# Audio_Moduloop.net
KiCad netlist of a schematic drawn in Altium Designer
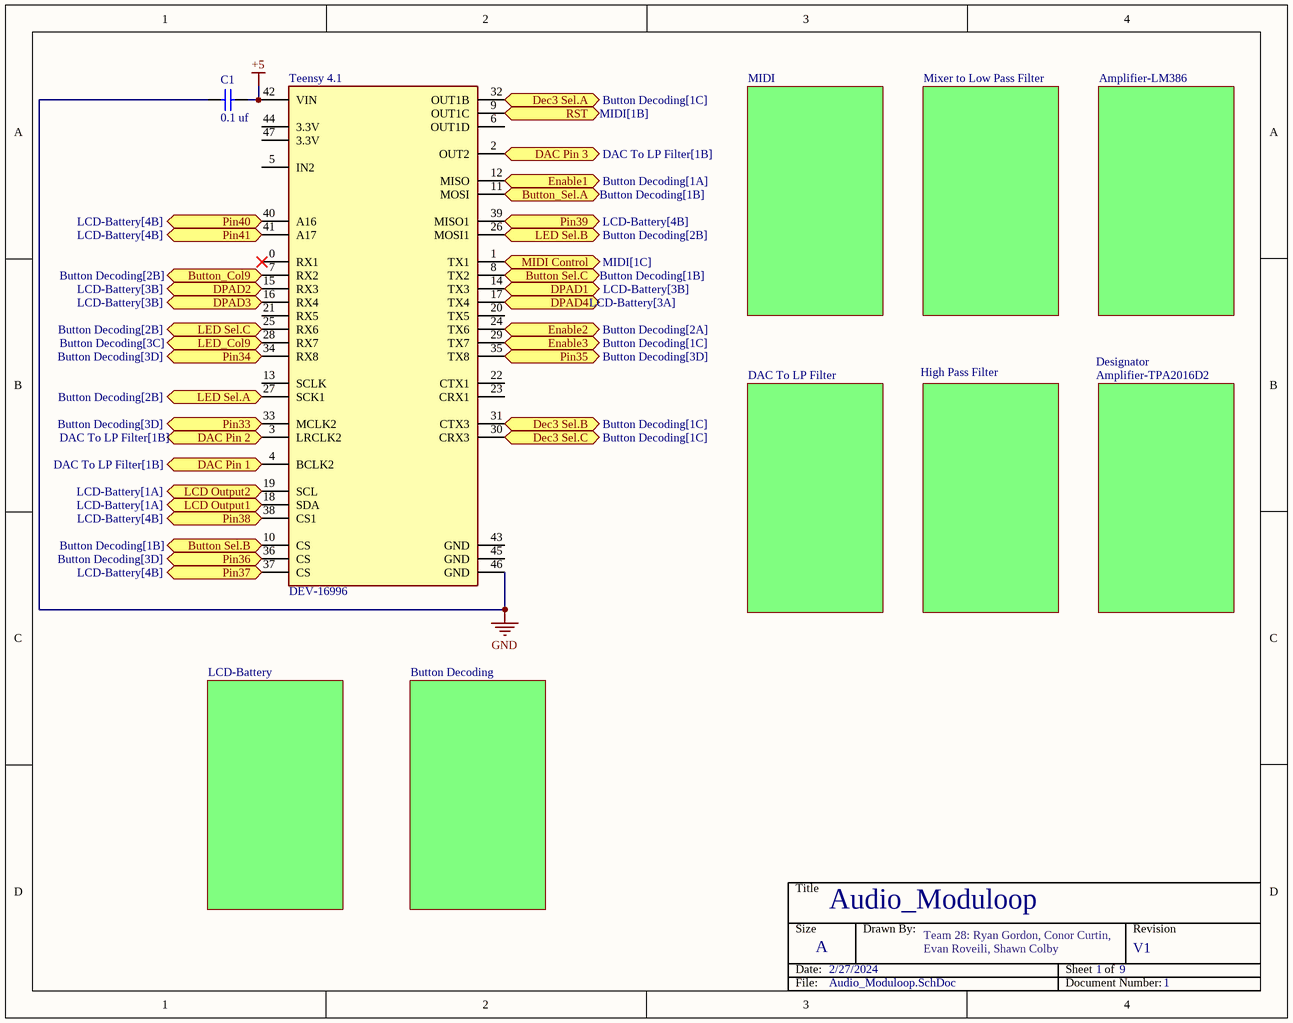
[diagram p0: Audio_Moduloop.SchDoc]

(export (version "E")
  (design (tool "Eeschema 10.0.6"))
  (components
    (comp (ref "C1")
      (value "0.1 uf")
      (footprint "CAPC2013X135X45ML10T25")
      (description "Chip Capacitor, 0.1 uF, +/- 10%, 50 V, -55 to 125 degC, 0805 (2012 Metric), RoHS, Tape and Reel")
      (fields (field (name "VOLTAGE") "50V") (field (name "TOLERANCE") "10%"))
      (libsource (lib "Altium Content Vault") (part "CAP-NP-2"))
    )
    (comp (ref "Teensy 4.1")
      (value "DEV-16996")
      (footprint "FP-DEV-16996-MFG")
      (description "TEENSY 4.1 (HEADERS)")
      (libsource (lib "Altium Content Vault") (part "080115a1ce54750370cf87ec145ee29"))
    )
  )
  (nets
    (net (code "1") (name "+5") (class "Default")
      (node (ref "C1") (pin "1") (pinfunction "1_1") (pintype "passive"))
      (node (ref "Teensy 4.1") (pin "42") (pinfunction "VIN_42") (pintype "passive"))
    )
    (net (code "2") (name "/Button Sel.B") (class "Default")
      (node (ref "Teensy 4.1") (pin "10") (pinfunction "CS_10") (pintype "passive"))
    )
    (net (code "4") (name "/Button Sel.C") (class "Default")
      (node (ref "Teensy 4.1") (pin "8") (pinfunction "TX2_8") (pintype "passive"))
    )
    (net (code "6") (name "/Button_Col9") (class "Default")
      (node (ref "Teensy 4.1") (pin "7") (pinfunction "RX2_7") (pintype "passive"))
    )
    (net (code "7") (name "/Button_Sel.A") (class "Default")
      (node (ref "Teensy 4.1") (pin "11") (pinfunction "MOSI_11") (pintype "passive"))
    )
    (net (code "10") (name "/DAC Pin 1") (class "Default")
      (node (ref "Teensy 4.1") (pin "4") (pinfunction "BCLK2_4") (pintype "passive"))
    )
    (net (code "11") (name "/DAC Pin 2") (class "Default")
      (node (ref "Teensy 4.1") (pin "3") (pinfunction "LRCLK2_3") (pintype "passive"))
    )
    (net (code "19") (name "/DAC Pin 3") (class "Default")
      (node (ref "Teensy 4.1") (pin "2") (pinfunction "OUT2_2") (pintype "passive"))
    )
    (net (code "20") (name "/DPAD1") (class "Default")
      (node (ref "Teensy 4.1") (pin "14") (pinfunction "TX3_14") (pintype "passive"))
    )
    (net (code "21") (name "/DPAD2") (class "Default")
      (node (ref "Teensy 4.1") (pin "15") (pinfunction "RX3_15") (pintype "passive"))
    )
    (net (code "23") (name "/DPAD3") (class "Default")
      (node (ref "Teensy 4.1") (pin "16") (pinfunction "RX4_16") (pintype "passive"))
    )
    (net (code "24") (name "/DPAD4") (class "Default")
      (node (ref "Teensy 4.1") (pin "17") (pinfunction "TX4_17") (pintype "passive"))
    )
    (net (code "26") (name "/Dec3 Sel.A") (class "Default")
      (node (ref "Teensy 4.1") (pin "32") (pinfunction "OUT1B_32") (pintype "passive"))
    )
    (net (code "27") (name "/Dec3 Sel.B") (class "Default")
      (node (ref "Teensy 4.1") (pin "31") (pinfunction "CTX3_31") (pintype "passive"))
    )
    (net (code "29") (name "/Dec3 Sel.C") (class "Default")
      (node (ref "Teensy 4.1") (pin "30") (pinfunction "CRX3_30") (pintype "passive"))
    )
    (net (code "30") (name "/Enable1") (class "Default")
      (node (ref "Teensy 4.1") (pin "12") (pinfunction "MISO_12") (pintype "passive"))
    )
    (net (code "31") (name "/Enable2") (class "Default")
      (node (ref "Teensy 4.1") (pin "24") (pinfunction "TX6_24") (pintype "passive"))
    )
    (net (code "33") (name "/Enable3") (class "Default")
      (node (ref "Teensy 4.1") (pin "29") (pinfunction "TX7_29") (pintype "passive"))
    )
    (net (code "34") (name "/LCD Output1") (class "Default")
      (node (ref "Teensy 4.1") (pin "18") (pinfunction "SDA_18") (pintype "passive"))
    )
    (net (code "36") (name "/LCD Output2") (class "Default")
      (node (ref "Teensy 4.1") (pin "19") (pinfunction "SCL_19") (pintype "passive"))
    )
    (net (code "37") (name "/LED Sel.A") (class "Default")
      (node (ref "Teensy 4.1") (pin "27") (pinfunction "SCK1_27") (pintype "passive"))
    )
    (net (code "38") (name "/LED Sel.B") (class "Default")
      (node (ref "Teensy 4.1") (pin "26") (pinfunction "MOSI1_26") (pintype "passive"))
    )
    (net (code "39") (name "/LED Sel.C") (class "Default")
      (node (ref "Teensy 4.1") (pin "25") (pinfunction "RX6_25") (pintype "passive"))
    )
    (net (code "40") (name "/LED_Col9") (class "Default")
      (node (ref "Teensy 4.1") (pin "28") (pinfunction "RX7_28") (pintype "passive"))
    )
    (net (code "41") (name "/MIDI Control") (class "Default")
      (node (ref "Teensy 4.1") (pin "1") (pinfunction "TX1_1") (pintype "passive"))
    )
    (net (code "42") (name "/Pin33") (class "Default")
      (node (ref "Teensy 4.1") (pin "33") (pinfunction "MCLK2_33") (pintype "passive"))
    )
    (net (code "43") (name "/Pin34") (class "Default")
      (node (ref "Teensy 4.1") (pin "34") (pinfunction "RX8_34") (pintype "passive"))
    )
    (net (code "44") (name "/Pin35") (class "Default")
      (node (ref "Teensy 4.1") (pin "35") (pinfunction "TX8_35") (pintype "passive"))
    )
    (net (code "45") (name "/Pin36") (class "Default")
      (node (ref "Teensy 4.1") (pin "36") (pinfunction "CS_36") (pintype "passive"))
    )
    (net (code "46") (name "/Pin37") (class "Default")
      (node (ref "Teensy 4.1") (pin "37") (pinfunction "CS_37") (pintype "passive"))
    )
    (net (code "47") (name "/Pin38") (class "Default")
      (node (ref "Teensy 4.1") (pin "38") (pinfunction "CS1_38") (pintype "passive"))
    )
    (net (code "48") (name "/Pin39") (class "Default")
      (node (ref "Teensy 4.1") (pin "39") (pinfunction "MISO1_39") (pintype "passive"))
    )
    (net (code "49") (name "/Pin40") (class "Default")
      (node (ref "Teensy 4.1") (pin "40") (pinfunction "A16_40") (pintype "passive"))
    )
    (net (code "50") (name "/Pin41") (class "Default")
      (node (ref "Teensy 4.1") (pin "41") (pinfunction "A17_41") (pintype "passive"))
    )
    (net (code "51") (name "/RST") (class "Default")
      (node (ref "Teensy 4.1") (pin "9") (pinfunction "OUT1C_9") (pintype "passive"))
    )
    (net (code "52") (name "GND") (class "Default")
      (node (ref "C1") (pin "2") (pinfunction "2_2") (pintype "passive"))
      (node (ref "Teensy 4.1") (pin "46") (pinfunction "GND_46") (pintype "passive"))
    )
    (net (code "53") (name "unconnected-(Teensy 4.1-3.3V-Pad44)") (class "Default")
      (node (ref "Teensy 4.1") (pin "44") (pinfunction "3.3V_44") (pintype "passive"))
    )
    (net (code "54") (name "unconnected-(Teensy 4.1-3.3V-Pad47)") (class "Default")
      (node (ref "Teensy 4.1") (pin "47") (pinfunction "3.3V_47") (pintype "passive"))
    )
    (net (code "55") (name "unconnected-(Teensy 4.1-CRX1-Pad23)") (class "Default")
      (node (ref "Teensy 4.1") (pin "23") (pinfunction "CRX1_23") (pintype "passive"))
    )
    (net (code "56") (name "unconnected-(Teensy 4.1-CTX1-Pad22)") (class "Default")
      (node (ref "Teensy 4.1") (pin "22") (pinfunction "CTX1_22") (pintype "passive"))
    )
    (net (code "57") (name "unconnected-(Teensy 4.1-GND-Pad43)") (class "Default")
      (node (ref "Teensy 4.1") (pin "43") (pinfunction "GND_43") (pintype "passive"))
    )
    (net (code "58") (name "unconnected-(Teensy 4.1-GND-Pad45)") (class "Default")
      (node (ref "Teensy 4.1") (pin "45") (pinfunction "GND_45") (pintype "passive"))
    )
    (net (code "59") (name "unconnected-(Teensy 4.1-IN2-Pad5)") (class "Default")
      (node (ref "Teensy 4.1") (pin "5") (pinfunction "IN2_5") (pintype "passive"))
    )
    (net (code "60") (name "unconnected-(Teensy 4.1-OUT1D-Pad6)") (class "Default")
      (node (ref "Teensy 4.1") (pin "6") (pinfunction "OUT1D_6") (pintype "passive"))
    )
    (net (code "61") (name "unconnected-(Teensy 4.1-RX1-Pad0)") (class "Default")
      (node (ref "Teensy 4.1") (pin "0") (pinfunction "RX1_0") (pintype "passive+no_connect"))
    )
    (net (code "62") (name "unconnected-(Teensy 4.1-RX5-Pad21)") (class "Default")
      (node (ref "Teensy 4.1") (pin "21") (pinfunction "RX5_21") (pintype "passive"))
    )
    (net (code "63") (name "unconnected-(Teensy 4.1-SCLK-Pad13)") (class "Default")
      (node (ref "Teensy 4.1") (pin "13") (pinfunction "SCLK_13") (pintype "passive"))
    )
    (net (code "64") (name "unconnected-(Teensy 4.1-TX5-Pad20)") (class "Default")
      (node (ref "Teensy 4.1") (pin "20") (pinfunction "TX5_20") (pintype "passive"))
    )
  )
)
